# JacdacBrainRP2040_59.net
KiCad netlist of a schematic drawn in Altium Designer
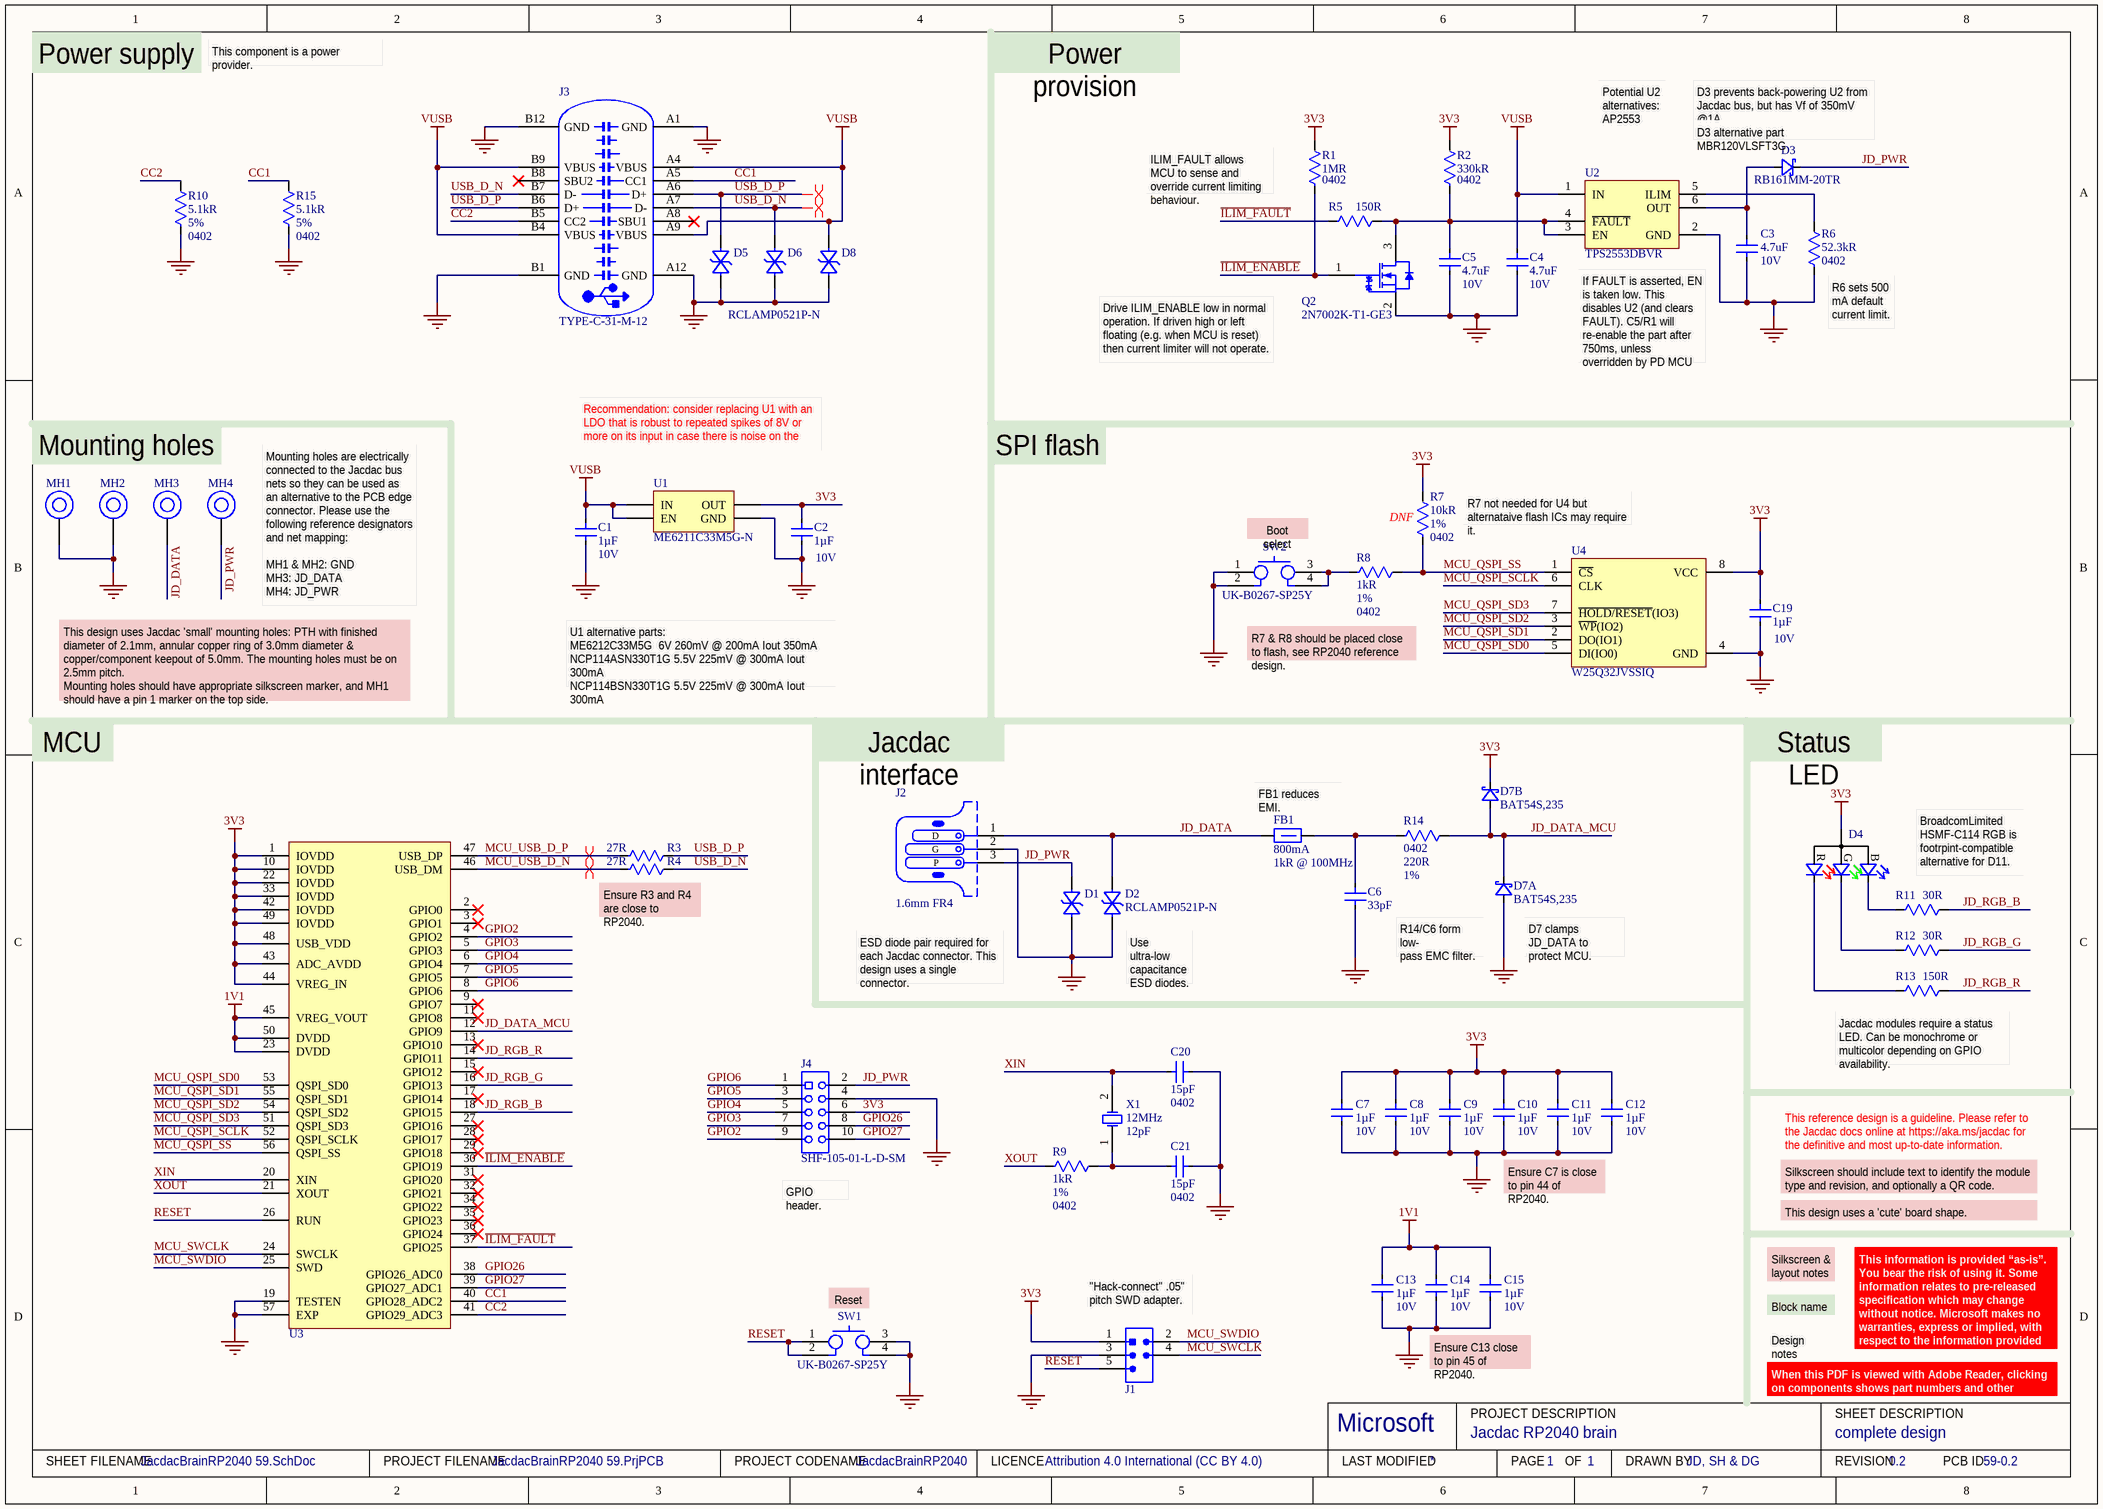
[diagram p0: JacdacBrainRP2040 59.SchDoc]

(export (version "E")
  (design (tool "Eeschema 10.0.6"))
  (components
    (comp (ref "C1")
      (value "CL05A105KP5NNNC")
      (footprint "C0402_0.55MM - without outline")
      (description "CAP CER 1UF 10V X5R 0402")
      (fields
        (field (name "MANUFACTURER") "Samsung")
        (field (name "TOLERANCE") "10%")
        (field (name "CAPACITANCE") "1µF")
        (field (name "VOLTAGE RATING") "10V")
        (field (name "CREATED") "DG")
        (field (name "CHECKED") "?")
      )
      (libsource (lib "Samsung") (part "CL05A105KP5NNNC"))
    )
    (comp (ref "C2")
      (value "CL05A105KP5NNNC")
      (footprint "C0402_0.55MM - without outline")
      (description "CAP CER 1UF 10V X5R 0402")
      (fields
        (field (name "MANUFACTURER") "Samsung")
        (field (name "TOLERANCE") "10%")
        (field (name "CAPACITANCE") "1µF")
        (field (name "VOLTAGE RATING") "10V")
        (field (name "CREATED") "DG")
        (field (name "CHECKED") "?")
      )
      (libsource (lib "Samsung") (part "CL05A105KP5NNNC"))
    )
    (comp (ref "C3")
      (value "CL05A475MP5NRNC")
      (footprint "R0402 - Without outline")
      (description "CAP CER 4.7UF 10V X5R 0402")
      (fields
        (field (name "MANUFACTURER") "Samsung")
        (field (name "TOLERANCE") "20%")
        (field (name "CAPACITANCE") "4.7uF")
        (field (name "VOLTAGE RATING") "10V")
        (field (name "CREATED BY") "D. Gakure")
        (field (name "CHECKED BY") "?")
      )
      (libsource (lib "Samsung") (part "CL05A475MP5NRNC"))
    )
    (comp (ref "C4")
      (value "CL05A475MP5NRNC")
      (footprint "R0402 - Without outline")
      (description "CAP CER 4.7UF 10V X5R 0402")
      (fields
        (field (name "MANUFACTURER") "Samsung")
        (field (name "TOLERANCE") "20%")
        (field (name "CAPACITANCE") "4.7uF")
        (field (name "VOLTAGE RATING") "10V")
        (field (name "CREATED BY") "D. Gakure")
        (field (name "CHECKED BY") "?")
      )
      (libsource (lib "Samsung") (part "CL05A475MP5NRNC"))
    )
    (comp (ref "C5")
      (value "CL05A475MP5NRNC")
      (footprint "R0402 - Without outline")
      (description "CAP CER 4.7UF 10V X5R 0402")
      (fields
        (field (name "MANUFACTURER") "Samsung")
        (field (name "TOLERANCE") "20%")
        (field (name "CAPACITANCE") "4.7uF")
        (field (name "VOLTAGE RATING") "10V")
        (field (name "CREATED BY") "D. Gakure")
        (field (name "CHECKED BY") "?")
      )
      (libsource (lib "Samsung") (part "CL05A475MP5NRNC"))
    )
    (comp (ref "C6")
      (value "CL05C330JB51PNC")
      (footprint "C0402_0.55MM - without outline")
      (description "CAP CER 33PF 50V NP0 0402")
      (fields
        (field (name "MANUFACTURER") "Samsung")
        (field (name "TOLERANCE") "5%")
        (field (name "CAPACITANCE") "33pF")
        (field (name "CHECKED") "?")
        (field (name "CREATED") "DG")
      )
      (libsource (lib "Samsung") (part "CL05C330JB51PNC"))
    )
    (comp (ref "C7")
      (value "CL05A105KP5NNNC")
      (footprint "C0402_0.55MM - without outline")
      (description "CAP CER 1UF 10V X5R 0402")
      (fields
        (field (name "MANUFACTURER") "Samsung")
        (field (name "TOLERANCE") "10%")
        (field (name "CAPACITANCE") "1µF")
        (field (name "VOLTAGE RATING") "10V")
        (field (name "CREATED") "DG")
        (field (name "CHECKED") "?")
      )
      (libsource (lib "Samsung") (part "CL05A105KP5NNNC"))
    )
    (comp (ref "C8")
      (value "CL05A105KP5NNNC")
      (footprint "C0402_0.55MM - without outline")
      (description "CAP CER 1UF 10V X5R 0402")
      (fields
        (field (name "MANUFACTURER") "Samsung")
        (field (name "TOLERANCE") "10%")
        (field (name "CAPACITANCE") "1µF")
        (field (name "VOLTAGE RATING") "10V")
        (field (name "CREATED") "DG")
        (field (name "CHECKED") "?")
      )
      (libsource (lib "Samsung") (part "CL05A105KP5NNNC"))
    )
    (comp (ref "C9")
      (value "CL05A105KP5NNNC")
      (footprint "C0402_0.55MM - without outline")
      (description "CAP CER 1UF 10V X5R 0402")
      (fields
        (field (name "MANUFACTURER") "Samsung")
        (field (name "TOLERANCE") "10%")
        (field (name "CAPACITANCE") "1µF")
        (field (name "VOLTAGE RATING") "10V")
        (field (name "CREATED") "DG")
        (field (name "CHECKED") "?")
      )
      (libsource (lib "Samsung") (part "CL05A105KP5NNNC"))
    )
    (comp (ref "C10")
      (value "CL05A105KP5NNNC")
      (footprint "C0402_0.55MM - without outline")
      (description "CAP CER 1UF 10V X5R 0402")
      (fields
        (field (name "MANUFACTURER") "Samsung")
        (field (name "TOLERANCE") "10%")
        (field (name "CAPACITANCE") "1µF")
        (field (name "VOLTAGE RATING") "10V")
        (field (name "CREATED") "DG")
        (field (name "CHECKED") "?")
      )
      (libsource (lib "Samsung") (part "CL05A105KP5NNNC"))
    )
    (comp (ref "C11")
      (value "CL05A105KP5NNNC")
      (footprint "C0402_0.55MM - without outline")
      (description "CAP CER 1UF 10V X5R 0402")
      (fields
        (field (name "MANUFACTURER") "Samsung")
        (field (name "TOLERANCE") "10%")
        (field (name "CAPACITANCE") "1µF")
        (field (name "VOLTAGE RATING") "10V")
        (field (name "CREATED") "DG")
        (field (name "CHECKED") "?")
      )
      (libsource (lib "Samsung") (part "CL05A105KP5NNNC"))
    )
    (comp (ref "C12")
      (value "CL05A105KP5NNNC")
      (footprint "C0402_0.55MM - without outline")
      (description "CAP CER 1UF 10V X5R 0402")
      (fields
        (field (name "MANUFACTURER") "Samsung")
        (field (name "TOLERANCE") "10%")
        (field (name "CAPACITANCE") "1µF")
        (field (name "VOLTAGE RATING") "10V")
        (field (name "CREATED") "DG")
        (field (name "CHECKED") "?")
      )
      (libsource (lib "Samsung") (part "CL05A105KP5NNNC"))
    )
    (comp (ref "C13")
      (value "CL05A105KP5NNNC")
      (footprint "C0402_0.55MM - without outline")
      (description "CAP CER 1UF 10V X5R 0402")
      (fields
        (field (name "MANUFACTURER") "Samsung")
        (field (name "TOLERANCE") "10%")
        (field (name "CAPACITANCE") "1µF")
        (field (name "VOLTAGE RATING") "10V")
        (field (name "CREATED") "DG")
        (field (name "CHECKED") "?")
      )
      (libsource (lib "Samsung") (part "CL05A105KP5NNNC"))
    )
    (comp (ref "C14")
      (value "CL05A105KP5NNNC")
      (footprint "C0402_0.55MM - without outline")
      (description "CAP CER 1UF 10V X5R 0402")
      (fields
        (field (name "MANUFACTURER") "Samsung")
        (field (name "TOLERANCE") "10%")
        (field (name "CAPACITANCE") "1µF")
        (field (name "VOLTAGE RATING") "10V")
        (field (name "CREATED") "DG")
        (field (name "CHECKED") "?")
      )
      (libsource (lib "Samsung") (part "CL05A105KP5NNNC"))
    )
    (comp (ref "C15")
      (value "CL05A105KP5NNNC")
      (footprint "C0402_0.55MM - without outline")
      (description "CAP CER 1UF 10V X5R 0402")
      (fields
        (field (name "MANUFACTURER") "Samsung")
        (field (name "TOLERANCE") "10%")
        (field (name "CAPACITANCE") "1µF")
        (field (name "VOLTAGE RATING") "10V")
        (field (name "CREATED") "DG")
        (field (name "CHECKED") "?")
      )
      (libsource (lib "Samsung") (part "CL05A105KP5NNNC"))
    )
    (comp (ref "C19")
      (value "CL05A105KP5NNNC")
      (footprint "C0402_0.55MM - without outline")
      (description "CAP CER 1UF 10V X5R 0402")
      (fields
        (field (name "MANUFACTURER") "Samsung")
        (field (name "TOLERANCE") "10%")
        (field (name "CAPACITANCE") "1µF")
        (field (name "VOLTAGE RATING") "10V")
        (field (name "CREATED") "DG")
        (field (name "CHECKED") "?")
      )
      (libsource (lib "Samsung") (part "CL05A105KP5NNNC"))
    )
    (comp (ref "C20")
      (value "CL05C150JB5NNNC")
      (footprint "C0402_0.55MM - without outline")
      (description "CAP CER 15PF 50V C0G/NP0 0402")
      (fields
        (field (name "MANUFACTURER") "Samsung")
        (field (name "TOLERANCE") "5%")
        (field (name "CAPACITANCE") "15pF")
        (field (name "CASE/PACKAGE") "0402")
      )
      (libsource (lib "Samsung") (part "CL05C150JB5NNNC"))
    )
    (comp (ref "C21")
      (value "CL05C150JB5NNNC")
      (footprint "C0402_0.55MM - without outline")
      (description "CAP CER 15PF 50V C0G/NP0 0402")
      (fields
        (field (name "MANUFACTURER") "Samsung")
        (field (name "TOLERANCE") "5%")
        (field (name "CAPACITANCE") "15pF")
        (field (name "CASE/PACKAGE") "0402")
      )
      (libsource (lib "Samsung") (part "CL05C150JB5NNNC"))
    )
    (comp (ref "D1")
      (value "RCLAMP0521P-N")
      (footprint "TVS 0402 - L")
      (description "Bidirectional 5V (Max) 6V 16V 3.5A (8/20us) 0402 TVS RoHS")
      (fields
        (field (name "MANUFACTURER") "Born Semiconductor")
        (field (name "CREATED BY") "D Gakure")
        (field (name "CHECKED BY") "?")
      )
      (libsource (lib "BornSemiconductor") (part "RCLAMP0521P-N"))
    )
    (comp (ref "D2")
      (value "RCLAMP0521P-N")
      (footprint "TVS 0402 - L")
      (description "Bidirectional 5V (Max) 6V 16V 3.5A (8/20us) 0402 TVS RoHS")
      (fields
        (field (name "MANUFACTURER") "Born Semiconductor")
        (field (name "MANUFACTURER PART NUMBER") "RCLAMP0521P-N")
        (field (name "CREATED BY") "D Gakure")
        (field (name "CHECKED BY") "?")
      )
      (libsource (lib "BornSemiconductor") (part "RCLAMP0521P-N"))
    )
    (comp (ref "D3")
      (value "RB161MM-20TR")
      (footprint "SOD-123F")
      (description "ROHM - RB161MM-20TR - Schottky-Gleichrichterdiode, 20 V, 1 A, Einfach, SOD-123FL, 2 Pin(s), 350 mV")
      (fields (field (name "MANUFACTURER") "Rohm") (field (name "MANUFACTURER PART NUMBER") "RB161MM-20TR"))
      (libsource (lib "Rohm") (part "RB161MM-20TR"))
    )
    (comp (ref "D4")
      (value "TZ-P4-1615RGBTCA1-0.55T")
      (footprint "TZ-P4-1615RGBTCA1-0.55T")
      (description "1615 Light Emitting Diodes (LED) RoHS")
      (fields
        (field (name "MANUFACTURER") "TUOZHAN")
        (field (name "CREATED BY") "D. Gakure")
        (field (name "CHECKED BY") "?")
      )
      (libsource (lib "Tuozhan") (part "TZ-P4-1615RGBTCA1-0.55T"))
    )
    (comp (ref "D5")
      (value "RCLAMP0521P-N")
      (footprint "TVS 0402 - L")
      (description "Bidirectional 5V (Max) 6V 16V 3.5A (8/20us) 0402 TVS RoHS")
      (fields
        (field (name "MANUFACTURER") "Born Semiconductor")
        (field (name "CREATED BY") "D Gakure")
        (field (name "CHECKED BY") "?")
      )
      (libsource (lib "BornSemiconductor") (part "RCLAMP0521P-N"))
    )
    (comp (ref "D6")
      (value "RCLAMP0521P-N")
      (footprint "TVS 0402 - L")
      (description "Bidirectional 5V (Max) 6V 16V 3.5A (8/20us) 0402 TVS RoHS")
      (fields
        (field (name "MANUFACTURER") "Born Semiconductor")
        (field (name "CREATED BY") "D Gakure")
        (field (name "CHECKED BY") "?")
      )
      (libsource (lib "BornSemiconductor") (part "RCLAMP0521P-N"))
    )
    (comp (ref "D7")
      (value "BAT54S")
      (footprint "NXP-BAT54S-TO-236AB - without outline")
      (description "DIODE ARRAY SCHOTTKY 30V SOT23")
      (fields (field (name "MANUFACTURER") "Nexperia") (field (name "MANUFACTURER PART NUMBER") "BAT54S,235"))
      (libsource (lib "NXP") (part "BAT54S"))
    )
    (comp (ref "D8")
      (value "RCLAMP0521P-N")
      (footprint "TVS 0402 - L")
      (description "Bidirectional 5V (Max) 6V 16V 3.5A (8/20us) 0402 TVS RoHS")
      (fields
        (field (name "MANUFACTURER") "Born Semiconductor")
        (field (name "MANUFACTURER PART NUMBER") "RCLAMP0521P-N")
        (field (name "CREATED BY") "D Gakure")
        (field (name "CHECKED BY") "?")
      )
      (libsource (lib "BornSemiconductor") (part "RCLAMP0521P-N"))
    )
    (comp (ref "FB1")
      (value "TDK MPZ1608S102ATA00")
      (footprint "TDK MPZ1608 0.8mm - without outline")
      (description "0603 1k@100MHz 0.8A chip")
      (fields
        (field (name "TOLERANCE") "25%")
        (field (name "MANUFACTURER") "TDK")
        (field (name "CURRENT RATING") "800mA")
        (field (name "IMPEDANCE") "1kR @ 100MHz")
      )
      (libsource (lib "TDK") (part "TDK MPZ1608S102ATA00"))
    )
    (comp (ref "J1")
      (value "Hack Connect Mini 1.27 mm pitch 2-row")
      (footprint "HACK_CONNECT_MINI_5_X_1_27")
      (libsource (lib "generic-con") (part "HACK_CONNECT_MINI"))
    )
    (comp (ref "J2")
      (value "3 pin JACDAC edge connector")
      (footprint "JACDAC_EDGE_CONNECTOR_NO_TRACES")
      (description "3 pin Jacdac edge connector 1.27mm pitch")
      (fields
        (field (name "MANUFACTURER PART NUMBER") "JACDAC_EDGE_CONNECTOR")
        (field (name "PCB TYPE") "1.6mm FR4")
        (field (name "CHECKED BY") "?")
        (field (name "CREATED BY") "D. Gakure")
      )
      (libsource (lib "generic-con") (part "Jacdac edge connector"))
    )
    (comp (ref "J3")
      (value "TYPE-C-31-M-12")
      (footprint "TYPE-C-31-M-12")
      (description "USB - Type C Female 16 USB Connectors RoHS")
      (fields
        (field (name "MANUFACTURER") "Korean Hroparts Elec")
        (field (name "MANUFACTURER PART NUMBER") "TYPE-C-31-M-12")
      )
      (libsource (lib "KoreanHropartsElec") (part "TYPE-C-31-M-12"))
    )
    (comp (ref "J4")
      (value "SHF-105-01-L-D-SM-whitesch")
      (footprint "Samtec SHF-105-01-L-D-SM - NO SILKSCREEN")
      (description "Standard Card Edge Connectors .050 Mini Edge Card Connector, Vertical")
      (fields
        (field (name "MANUFACTURER") "Samtec")
        (field (name "MANUFACTURER PART NUMBER") "SHF-105-01-L-D-SM")
      )
      (libsource (lib "Samtec") (part "SHF-105-01-L-D-SM-whitesch"))
    )
    (comp (ref "MH1")
      (value "MH_5.0MMK_3.0MMC_2.1MMD_PTH")
      (footprint "MH_5.0MMK_3.0MMC_2.1MMD_PTH")
      (description "Mounting Hole 5.0mm keepout, 3.0mm annualar ring and 2.1mm Drill PTH")
      (libsource (lib "generic") (part "MH_5.0MMK_3.0MMC_2.1MMD_PTH"))
    )
    (comp (ref "MH2")
      (value "MH_5.0MMK_3.0MMC_2.1MMD_PTH")
      (footprint "MH_5.0MMK_3.0MMC_2.1MMD_PTH")
      (description "Mounting Hole 5.0mm keepout, 3.0mm annualar ring and 2.1mm Drill PTH")
      (libsource (lib "generic") (part "MH_5.0MMK_3.0MMC_2.1MMD_PTH"))
    )
    (comp (ref "MH3")
      (value "MH_5.0MMK_3.0MMC_2.1MMD_PTH")
      (footprint "MH_5.0MMK_3.0MMC_2.1MMD_PTH")
      (description "Mounting Hole 5.0mm keepout, 3.0mm annualar ring and 2.1mm Drill PTH")
      (libsource (lib "generic") (part "MH_5.0MMK_3.0MMC_2.1MMD_PTH"))
    )
    (comp (ref "MH4")
      (value "MH_5.0MMK_3.0MMC_2.1MMD_PTH")
      (footprint "MH_5.0MMK_3.0MMC_2.1MMD_PTH")
      (description "Mounting Hole 5.0mm keepout, 3.0mm annualar ring and 2.1mm Drill PTH")
      (libsource (lib "generic") (part "MH_5.0MMK_3.0MMC_2.1MMD_PTH"))
    )
    (comp (ref "Q2")
      (value "2N7002K-T1-GE3")
      (footprint "SOT-23-3 (TO-236)")
      (description "Trans MOSFET N-CH Si 60V 0.3A 3-Pin SOT-23 T/R")
      (fields
        (field (name "MANUFACTURER") "Vishay")
        (field (name "VOLTAGE") "60V")
        (field (name "MANUFACTURER PART NUMBER") "2N7002K-T1-GE3")
      )
      (libsource (lib "Vishay") (part "2N7002K-T1-GE3"))
    )
    (comp (ref "R1")
      (value "~")
      (footprint "R0402 - Without outline")
      (description "RES SMD 1M OHM 1% 1/16W 0402")
      (fields
        (field (name "MANUFACTURER") "Yageo")
        (field (name "MANUFACTURER PART NUMBER") "RC0402FR-071ML")
        (field (name "RESISTANCE") "1MR")
        (field (name "CASE CODE (IMPERIAL)") "0402")
        (field (name "CREATED BY") "D. Gakure")
        (field (name "CHECKED BY") "?")
      )
      (libsource (lib "Yageo") (part "RC0402FR-071ML"))
    )
    (comp (ref "R2")
      (value "RC0402FR-07330KL")
      (footprint "R0402 - Without outline")
      (description "RES SMD 330K OHM 1% 1/16W 0402")
      (fields
        (field (name "MANUFACTURER") "Yageo")
        (field (name "RESISTANCE") "330kR")
        (field (name "TOLERANCE") "1%")
        (field (name "SIZE CODE") "0402")
        (field (name "CREATED BY") "D Gakure")
        (field (name "CHECKED BY") "?")
      )
      (libsource (lib "Yageo") (part "RC0402FR-07330KL"))
    )
    (comp (ref "R3")
      (value "RC0402FR-0727RL")
      (footprint "R0402 - Without outline")
      (description "RES SMD 27 OHM 1% 1/16W 0402")
      (fields
        (field (name "MANUFACTURER") "Yageo")
        (field (name "TOLERANCE") "1%")
        (field (name "RESISTANCE") "27R")
      )
      (libsource (lib "Yageo") (part "RC0402FR-0727RL"))
    )
    (comp (ref "R4")
      (value "RC0402FR-0727RL")
      (footprint "R0402 - Without outline")
      (description "RES SMD 27 OHM 1% 1/16W 0402")
      (fields
        (field (name "MANUFACTURER") "Yageo")
        (field (name "TOLERANCE") "1%")
        (field (name "RESISTANCE") "27R")
      )
      (libsource (lib "Yageo") (part "RC0402FR-0727RL"))
    )
    (comp (ref "R5")
      (value "RC0402FR-07150RL")
      (footprint "R0402 - Without outline")
      (description "RES SMD 150 OHM 1% 1/16W 0402")
      (fields
        (field (name "MANUFACTURER") "Yageo")
        (field (name "RESISTANCE") "150R")
        (field (name "TOLERANCE") "1%")
        (field (name "CREATED BY") "D. Gakure")
        (field (name "CHECKED BY") "?")
      )
      (libsource (lib "Yageo") (part "RC0402FR-07150RL"))
    )
    (comp (ref "R6")
      (value "RC0402FR-0752K3L")
      (footprint "R0402 - Without outline")
      (description "RES SMD 52.3K OHM 1% 1/16W 0402")
      (fields
        (field (name "MANUFACTURER") "Yageo")
        (field (name "RESISTANCE") "52.3kR")
        (field (name "TOLERANCE") "1%")
        (field (name "CASE CODE (IMPERIAL)") "0402")
        (field (name "CREATED BY") "D. Gakure")
        (field (name "CHECKED BY") "?")
      )
      (libsource (lib "Yageo") (part "RC0402FR-0752K3L"))
    )
    (comp (ref "R7")
      (value "10k")
      (footprint "R0402 - Without outline")
      (description "RES SMD 10K OHM 1% 1/16W 0402")
      (fields
        (field (name "MANUFACTURER") "Yageo")
        (field (name "MANUFACTURER PART NUMBER") "RC0402FR-0710KL")
        (field (name "RESISTANCE") "10kR")
        (field (name "TOLERANCE") "1%")
        (field (name "CASE CODE (IMPERIAL)") "0402")
        (field (name "CHECKED") "?")
        (field (name "CREATED") "DG")
      )
      (libsource (lib "Yageo") (part "RC0402FR-0710KL"))
    )
    (comp (ref "R8")
      (value "RC0402FR-071KL")
      (footprint "R0402 - Without outline")
      (description "RES SMD 1K OHM 1% 1/16W 0402")
      (fields
        (field (name "MANUFACTURER") "Yageo")
        (field (name "RESISTANCE") "1kR")
        (field (name "TOLERANCE") "1%")
        (field (name "CASE CODE (IMPERIAL)") "0402")
        (field (name "CREATED") "D.G")
        (field (name "CHECKED") "?")
      )
      (libsource (lib "Yageo") (part "RC0402FR-071KL"))
    )
    (comp (ref "R9")
      (value "RC0402FR-071KL")
      (footprint "R0402 - Without outline")
      (description "RES SMD 1K OHM 1% 1/16W 0402")
      (fields
        (field (name "MANUFACTURER") "Yageo")
        (field (name "RESISTANCE") "1kR")
        (field (name "TOLERANCE") "1%")
        (field (name "CASE CODE (IMPERIAL)") "0402")
        (field (name "CREATED") "D.G")
        (field (name "CHECKED") "?")
      )
      (libsource (lib "Yageo") (part "RC0402FR-071KL"))
    )
    (comp (ref "R10")
      (value "RC0402JR-075K1L")
      (footprint "R0402 - Without outline")
      (description "RES SMD 5.1K OHM 5% 1/16W 0402")
      (fields
        (field (name "MANUFACTURER") "Yageo")
        (field (name "RESISTANCE") "5.1kR")
        (field (name "TOLERANCE") "5%")
        (field (name "CASE CODE (IMPERIAL)") "0402")
        (field (name "CREATED BY") "D. Gakure")
        (field (name "CHECKED BY") "?")
      )
      (libsource (lib "Yageo") (part "RC0402JR-075K1L"))
    )
    (comp (ref "R11")
      (value "RC0402FR-0730RL")
      (footprint "R0402 - Without outline")
      (description "RES SMD 30 OHM 1% 1/16W 0402")
      (fields
        (field (name "MANUFACTURER") "Yageo")
        (field (name "RESISTANCE") "30R")
        (field (name "TOLERANCE") "1%")
        (field (name "CREATED BY") "D. Gakure")
        (field (name "CHECKED BY") "?")
      )
      (libsource (lib "Yageo") (part "RC0402FR-0730RL"))
    )
    (comp (ref "R12")
      (value "RC0402FR-0730RL")
      (footprint "R0402 - Without outline")
      (description "RES SMD 30 OHM 1% 1/16W 0402")
      (fields
        (field (name "MANUFACTURER") "Yageo")
        (field (name "RESISTANCE") "30R")
        (field (name "TOLERANCE") "1%")
        (field (name "CREATED BY") "D. Gakure")
        (field (name "CHECKED BY") "?")
      )
      (libsource (lib "Yageo") (part "RC0402FR-0730RL"))
    )
    (comp (ref "R13")
      (value "RC0402FR-07150RL")
      (footprint "R0402 - Without outline")
      (description "RES SMD 150 OHM 1% 1/16W 0402")
      (fields
        (field (name "MANUFACTURER") "Yageo")
        (field (name "RESISTANCE") "150R")
        (field (name "TOLERANCE") "1%")
        (field (name "CREATED BY") "D. Gakure")
        (field (name "CHECKED BY") "?")
      )
      (libsource (lib "Yageo") (part "RC0402FR-07150RL"))
    )
    (comp (ref "R14")
      (value "RC0402FR-07220RL")
      (footprint "R0402 - Without outline")
      (description "RES SMD 220 OHM 1% 1/16W 0402")
      (fields
        (field (name "MANUFACTURER") "Yageo")
        (field (name "CASE CODE (IMPERIAL)") "0402")
        (field (name "RESISTANCE") "220R")
        (field (name "TOLERANCE") "1%")
        (field (name "CREATED") "D.G")
        (field (name "CHECKED") "?")
      )
      (libsource (lib "Yageo") (part "RC0402FR-07220RL"))
    )
    (comp (ref "R15")
      (value "RC0402JR-075K1L")
      (footprint "R0402 - Without outline")
      (description "RES SMD 5.1K OHM 5% 1/16W 0402")
      (fields
        (field (name "MANUFACTURER") "Yageo")
        (field (name "RESISTANCE") "5.1kR")
        (field (name "TOLERANCE") "5%")
        (field (name "CASE CODE (IMPERIAL)") "0402")
        (field (name "CREATED BY") "D. Gakure")
        (field (name "CHECKED BY") "?")
      )
      (libsource (lib "Yageo") (part "RC0402JR-075K1L"))
    )
    (comp (ref "SW1")
      (value "UK-B0267-SP25Y")
      (footprint "USAKRO-UK-B0267-SP25Y")
      (description "SWITCH TACTILE SSPST 50mA @ 12VDC")
      (fields
        (field (name "MANUFACTURER") "USAKRO")
        (field (name "MANUFACTURER PART NUMBER") "UK-B0267-SP25Y")
      )
      (libsource (lib "Usakro") (part "UK-B0267-SP25Y"))
    )
    (comp (ref "SW2")
      (value "UK-B0267-SP25Y")
      (footprint "USAKRO-UK-B0267-SP25Y")
      (description "SWITCH TACTILE SSPST 50mA @ 12VDC")
      (fields
        (field (name "MANUFACTURER") "USAKRO")
        (field (name "MANUFACTURER PART NUMBER") "UK-B0267-SP25Y")
      )
      (libsource (lib "Usakro") (part "UK-B0267-SP25Y"))
    )
    (comp (ref "U1")
      (value "ME6211C33M5G-N")
      (footprint "MICRONE-SOT23-5")
      (description "6V 260mV @ 200mA(typ) - - Fixed 3.3V SOT-23-5 Linear Voltage Regulators (LDO) ROHS")
      (fields
        (field (name "MANUFACTURER") "MICRONE(Nanjing Micro One Elec)")
        (field (name "MANUFACTURER PART NUMBER") "ME6211C33M5G-N")
        (field (name "CREATED") "DG")
        (field (name "CHECKED") "?")
      )
      (libsource (lib "MICRONE(NanjingMicroOneElec)") (part "ME6211C33M5G-N"))
    )
    (comp (ref "U2")
      (value "TPS2553DBVR")
      (footprint "TI-TPS2553 - without_outline")
      (description "IC PWR SWITCH N-CHAN 1:1 SOT23-6")
      (fields
        (field (name "MANUFACTURER") "Texas Instruments")
        (field (name "MANUFACTURER PART NUMBER") "TPS2553DBVR")
      )
      (libsource (lib "TexasInstruments") (part "TPS2553DBVR"))
    )
    (comp (ref "U3")
      (value "RP2040")
      (footprint "RP2040")
      (description "QFN-56_7x7 MCU")
      (fields (field (name "MANUFACTURER") "Raspberry Pi"))
      (libsource (lib "RaspberryPi") (part "RP2040"))
    )
    (comp (ref "U4")
      (value "~")
      (footprint "8-SOIC")
      (description "FLASH - NOR Memory IC 32Mb (4M x 8) SPI - Quad I/O 133 MHz 8-SOIC")
      (fields
        (field (name "MANUFACTURER") "Winbond")
        (field (name "MANUFACTURER PART NUMBER") "W25Q32JVSSIQ")
      )
      (libsource (lib "WinbondElectronics") (part "W25Q32JVSSIQ"))
    )
    (comp (ref "X1")
      (value "12MHz")
      (footprint "SMD-5032_2P")
      (description "12MHz ±30ppm 12pF 50Ω SMD-5032_2P SMD Crystal Resonators RoHS")
      (fields
        (field (name "MANUFACTURER") "TXC")
        (field (name "MANUFACTURER PART NUMBER") "7A12000053")
        (field (name "LOAD CAPACITANCE") "12pF")
      )
      (libsource (lib "TXC") (part "7A12000053"))
    )
  )
  (nets
    (net (code "1") (name "/CC1") (class "Default")
      (node (ref "J3") (pin "A5") (pinfunction "CC1_A5") (pintype "passive"))
      (node (ref "R15") (pin "1") (pinfunction "1_1") (pintype "passive"))
      (node (ref "U3") (pin "40") (pinfunction "GPIO28_ADC2_40") (pintype "passive"))
    )
    (net (code "2") (name "/CC2") (class "Default")
      (node (ref "J3") (pin "B5") (pinfunction "CC2_B5") (pintype "passive"))
      (node (ref "R10") (pin "1") (pinfunction "1_1") (pintype "passive"))
      (node (ref "U3") (pin "41") (pinfunction "GPIO29_ADC3_41") (pintype "passive"))
    )
    (net (code "3") (name "/GPIO2") (class "Default")
      (node (ref "J4") (pin "9") (pinfunction "9_9") (pintype "passive"))
      (node (ref "U3") (pin "4") (pinfunction "GPIO2_4") (pintype "passive"))
    )
    (net (code "4") (name "/GPIO3") (class "Default")
      (node (ref "J4") (pin "7") (pinfunction "7_7") (pintype "passive"))
      (node (ref "U3") (pin "5") (pinfunction "GPIO3_5") (pintype "passive"))
    )
    (net (code "5") (name "/GPIO4") (class "Default")
      (node (ref "J4") (pin "5") (pinfunction "5_5") (pintype "passive"))
      (node (ref "U3") (pin "6") (pinfunction "GPIO4_6") (pintype "passive"))
    )
    (net (code "6") (name "/GPIO5") (class "Default")
      (node (ref "J4") (pin "3") (pinfunction "3_3") (pintype "passive"))
      (node (ref "U3") (pin "7") (pinfunction "GPIO5_7") (pintype "passive"))
    )
    (net (code "7") (name "/GPIO6") (class "Default")
      (node (ref "J4") (pin "1") (pinfunction "1_1") (pintype "passive"))
      (node (ref "U3") (pin "8") (pinfunction "GPIO6_8") (pintype "passive"))
    )
    (net (code "8") (name "/GPIO26") (class "Default")
      (node (ref "J4") (pin "8") (pinfunction "8_8") (pintype "passive"))
      (node (ref "U3") (pin "38") (pinfunction "GPIO26_ADC0_38") (pintype "passive"))
    )
    (net (code "9") (name "/GPIO27") (class "Default")
      (node (ref "J4") (pin "10") (pinfunction "10_10") (pintype "passive"))
      (node (ref "U3") (pin "39") (pinfunction "GPIO27_ADC1_39") (pintype "passive"))
    )
    (net (code "10") (name "/JD_DATA") (class "Default")
      (node (ref "D2") (pin "1") (pinfunction "K_1") (pintype "passive"))
      (node (ref "FB1") (pin "1") (pinfunction "1_1") (pintype "passive"))
      (node (ref "J2") (pin "1") (pinfunction "D_1") (pintype "passive"))
      (node (ref "MH3") (pin "1") (pinfunction "1_1") (pintype "passive"))
    )
    (net (code "11") (name "/JD_DATA_MCU") (class "Default")
      (node (ref "D7") (pin "3") (pinfunction "A_3") (pintype "passive"))
      (node (ref "R14") (pin "1") (pinfunction "1_1") (pintype "passive"))
      (node (ref "U3") (pin "12") (pinfunction "GPIO9_12") (pintype "passive"))
    )
    (net (code "12") (name "/JD_PWR") (class "Default")
      (node (ref "D1") (pin "1") (pinfunction "K_1") (pintype "passive"))
      (node (ref "D3") (pin "1") (pinfunction "K_1") (pintype "passive"))
      (node (ref "J2") (pin "3") (pinfunction "P_3") (pintype "passive"))
      (node (ref "J4") (pin "2") (pinfunction "2_2") (pintype "passive"))
      (node (ref "MH4") (pin "1") (pinfunction "1_1") (pintype "passive"))
    )
    (net (code "13") (name "/JD_RGB_B") (class "Default")
      (node (ref "R11") (pin "2") (pinfunction "2_2") (pintype "passive"))
      (node (ref "U3") (pin "18") (pinfunction "GPIO15_18") (pintype "passive"))
    )
    (net (code "14") (name "/JD_RGB_G") (class "Default")
      (node (ref "R12") (pin "2") (pinfunction "2_2") (pintype "passive"))
      (node (ref "U3") (pin "16") (pinfunction "GPIO13_16") (pintype "passive"))
    )
    (net (code "15") (name "/JD_RGB_R") (class "Default")
      (node (ref "R13") (pin "2") (pinfunction "2_2") (pintype "passive"))
      (node (ref "U3") (pin "14") (pinfunction "GPIO11_14") (pintype "passive"))
    )
    (net (code "16") (name "/MCU_QSPI_SCLK") (class "Default")
      (node (ref "U3") (pin "52") (pinfunction "QSPI_SCLK_52") (pintype "passive"))
      (node (ref "U4") (pin "6") (pinfunction "CLK_6") (pintype "passive"))
    )
    (net (code "17") (name "/MCU_QSPI_SD0") (class "Default")
      (node (ref "U3") (pin "53") (pinfunction "QSPI_SD0_53") (pintype "passive"))
      (node (ref "U4") (pin "5") (pinfunction "DI(IO0)_5") (pintype "passive"))
    )
    (net (code "18") (name "/MCU_QSPI_SD1") (class "Default")
      (node (ref "U3") (pin "55") (pinfunction "QSPI_SD1_55") (pintype "passive"))
      (node (ref "U4") (pin "2") (pinfunction "DO(IO1)_2") (pintype "passive"))
    )
    (net (code "19") (name "/MCU_QSPI_SD2") (class "Default")
      (node (ref "U3") (pin "54") (pinfunction "QSPI_SD2_54") (pintype "passive"))
      (node (ref "U4") (pin "3") (pinfunction "~{WP}(IO2)_3") (pintype "passive"))
    )
    (net (code "20") (name "/MCU_QSPI_SD3") (class "Default")
      (node (ref "U3") (pin "51") (pinfunction "QSPI_SD3_51") (pintype "passive"))
      (node (ref "U4") (pin "7") (pinfunction "~{HOLD/RESET}(IO3)_7") (pintype "passive"))
    )
    (net (code "21") (name "/MCU_QSPI_SS") (class "Default")
      (node (ref "R7") (pin "2") (pinfunction "2_2") (pintype "passive"))
      (node (ref "R8") (pin "1") (pinfunction "1_1") (pintype "passive"))
      (node (ref "U3") (pin "56") (pinfunction "QSPI_SS_56") (pintype "passive"))
      (node (ref "U4") (pin "1") (pinfunction "~{CS}_1") (pintype "passive"))
    )
    (net (code "22") (name "/MCU_SWCLK") (class "Default")
      (node (ref "J1") (pin "4") (pinfunction "SWCLK_4") (pintype "passive"))
      (node (ref "U3") (pin "24") (pinfunction "SWCLK_24") (pintype "passive"))
    )
    (net (code "23") (name "/MCU_SWDIO") (class "Default")
      (node (ref "J1") (pin "2") (pinfunction "SWDIO_2") (pintype "passive"))
      (node (ref "U3") (pin "25") (pinfunction "SWD_25") (pintype "passive"))
    )
    (net (code "24") (name "/MCU_USB_D_N") (class "Default")
      (node (ref "R4") (pin "1") (pinfunction "1_1") (pintype "passive"))
      (node (ref "U3") (pin "46") (pinfunction "USB_DM_46") (pintype "passive"))
    )
    (net (code "25") (name "/MCU_USB_D_P") (class "Default")
      (node (ref "R3") (pin "1") (pinfunction "1_1") (pintype "passive"))
      (node (ref "U3") (pin "47") (pinfunction "USB_DP_47") (pintype "passive"))
    )
    (net (code "26") (name "/RESET") (class "Default")
      (node (ref "J1") (pin "5") (pinfunction "RESET_5") (pintype "passive"))
      (node (ref "SW1") (pin "1") (pinfunction "1_1") (pintype "passive"))
      (node (ref "SW1") (pin "2") (pinfunction "2_2") (pintype "passive"))
      (node (ref "U3") (pin "26") (pinfunction "RUN_26") (pintype "passive"))
    )
    (net (code "27") (name "/USB_D_N") (class "Default")
      (node (ref "D6") (pin "1") (pinfunction "K_1") (pintype "passive"))
      (node (ref "J3") (pin "A7") (pinfunction "D-_A7") (pintype "passive"))
      (node (ref "J3") (pin "B7") (pinfunction "D-_B7") (pintype "passive"))
      (node (ref "R4") (pin "2") (pinfunction "2_2") (pintype "passive"))
    )
    (net (code "28") (name "/USB_D_P") (class "Default")
      (node (ref "D5") (pin "1") (pinfunction "K_1") (pintype "passive"))
      (node (ref "J3") (pin "A6") (pinfunction "D+_A6") (pintype "passive"))
      (node (ref "J3") (pin "B6") (pinfunction "D+_B6") (pintype "passive"))
      (node (ref "R3") (pin "2") (pinfunction "2_2") (pintype "passive"))
    )
    (net (code "29") (name "/XIN") (class "Default")
      (node (ref "C20") (pin "1") (pinfunction "1_1") (pintype "passive"))
      (node (ref "U3") (pin "20") (pinfunction "XIN_20") (pintype "passive"))
      (node (ref "X1") (pin "2") (pinfunction "OSC2/OSC1_2") (pintype "passive"))
    )
    (net (code "30") (name "/XOUT") (class "Default")
      (node (ref "R9") (pin "2") (pinfunction "2_2") (pintype "passive"))
      (node (ref "U3") (pin "21") (pinfunction "XOUT_21") (pintype "passive"))
    )
    (net (code "31") (name "/~{ILIM_ENABLE}") (class "Default")
      (node (ref "Q2") (pin "1") (pinfunction "G_1") (pintype "passive"))
      (node (ref "R1") (pin "2") (pinfunction "2_2") (pintype "passive"))
      (node (ref "U3") (pin "30") (pinfunction "GPIO19_30") (pintype "passive"))
    )
    (net (code "32") (name "/~{ILIM_FAULT}") (class "Default")
      (node (ref "R5") (pin "1") (pinfunction "1_1") (pintype "passive"))
      (node (ref "U3") (pin "37") (pinfunction "GPIO25_37") (pintype "passive"))
    )
    (net (code "33") (name "1V1") (class "Default")
      (node (ref "C13") (pin "2") (pinfunction "2_2") (pintype "passive"))
      (node (ref "C14") (pin "2") (pinfunction "2_2") (pintype "passive"))
      (node (ref "C15") (pin "2") (pinfunction "2_2") (pintype "passive"))
      (node (ref "U3") (pin "23") (pinfunction "DVDD_23") (pintype "passive"))
      (node (ref "U3") (pin "45") (pinfunction "VREG_VOUT_45") (pintype "passive"))
      (node (ref "U3") (pin "50") (pinfunction "DVDD_50") (pintype "passive"))
    )
    (net (code "34") (name "3V3") (class "Default")
      (node (ref "C10") (pin "2") (pinfunction "2_2") (pintype "passive"))
      (node (ref "C11") (pin "2") (pinfunction "2_2") (pintype "passive"))
      (node (ref "C12") (pin "2") (pinfunction "2_2") (pintype "passive"))
      (node (ref "C19") (pin "2") (pinfunction "2_2") (pintype "passive"))
      (node (ref "C2") (pin "2") (pinfunction "2_2") (pintype "passive"))
      (node (ref "C7") (pin "2") (pinfunction "2_2") (pintype "passive"))
      (node (ref "C8") (pin "2") (pinfunction "2_2") (pintype "passive"))
      (node (ref "C9") (pin "2") (pinfunction "2_2") (pintype "passive"))
      (node (ref "D4") (pin "1") (pinfunction "A_1") (pintype "passive"))
      (node (ref "D7") (pin "2") (pinfunction "K_2") (pintype "passive"))
      (node (ref "J1") (pin "1") (pinfunction "VCC_1") (pintype "passive"))
      (node (ref "J4") (pin "6") (pinfunction "6_6") (pintype "passive"))
      (node (ref "R1") (pin "1") (pinfunction "1_1") (pintype "passive"))
      (node (ref "R2") (pin "1") (pinfunction "1_1") (pintype "passive"))
      (node (ref "R7") (pin "1") (pinfunction "1_1") (pintype "passive"))
      (node (ref "U1") (pin "5") (pinfunction "OUT_5") (pintype "passive"))
      (node (ref "U3") (pin "1") (pinfunction "IOVDD_1") (pintype "passive"))
      (node (ref "U3") (pin "10") (pinfunction "IOVDD_10") (pintype "passive"))
      (node (ref "U3") (pin "22") (pinfunction "IOVDD_22") (pintype "passive"))
      (node (ref "U3") (pin "33") (pinfunction "IOVDD_33") (pintype "passive"))
      (node (ref "U3") (pin "42") (pinfunction "IOVDD_42") (pintype "passive"))
      (node (ref "U3") (pin "43") (pinfunction "ADC_AVDD_43") (pintype "passive"))
      (node (ref "U3") (pin "44") (pinfunction "VREG_IN_44") (pintype "passive"))
      (node (ref "U3") (pin "48") (pinfunction "USB_VDD_48") (pintype "passive"))
      (node (ref "U3") (pin "49") (pinfunction "IOVDD_49") (pintype "passive"))
      (node (ref "U4") (pin "8") (pinfunction "VCC_8") (pintype "power_in"))
    )
    (net (code "35") (name "GND") (class "Default")
      (node (ref "C1") (pin "1") (pinfunction "1_1") (pintype "passive"))
      (node (ref "C10") (pin "1") (pinfunction "1_1") (pintype "passive"))
      (node (ref "C11") (pin "1") (pinfunction "1_1") (pintype "passive"))
      (node (ref "C12") (pin "1") (pinfunction "1_1") (pintype "passive"))
      (node (ref "C13") (pin "1") (pinfunction "1_1") (pintype "passive"))
      (node (ref "C14") (pin "1") (pinfunction "1_1") (pintype "passive"))
      (node (ref "C15") (pin "1") (pinfunction "1_1") (pintype "passive"))
      (node (ref "C19") (pin "1") (pinfunction "1_1") (pintype "passive"))
      (node (ref "C2") (pin "1") (pinfunction "1_1") (pintype "passive"))
      (node (ref "C20") (pin "2") (pinfunction "2_2") (pintype "passive"))
      (node (ref "C21") (pin "2") (pinfunction "2_2") (pintype "passive"))
      (node (ref "C3") (pin "1") (pinfunction "1_1") (pintype "passive"))
      (node (ref "C4") (pin "1") (pinfunction "1_1") (pintype "passive"))
      (node (ref "C5") (pin "1") (pinfunction "1_1") (pintype "passive"))
      (node (ref "C6") (pin "1") (pinfunction "1_1") (pintype "passive"))
      (node (ref "C7") (pin "1") (pinfunction "1_1") (pintype "passive"))
      (node (ref "C8") (pin "1") (pinfunction "1_1") (pintype "passive"))
      (node (ref "C9") (pin "1") (pinfunction "1_1") (pintype "passive"))
      (node (ref "D1") (pin "2") (pinfunction "A_2") (pintype "passive"))
      (node (ref "D2") (pin "2") (pinfunction "A_2") (pintype "passive"))
      (node (ref "D5") (pin "2") (pinfunction "A_2") (pintype "passive"))
      (node (ref "D6") (pin "2") (pinfunction "A_2") (pintype "passive"))
      (node (ref "D7") (pin "1") (pinfunction "A_1") (pintype "passive"))
      (node (ref "D8") (pin "2") (pinfunction "A_2") (pintype "passive"))
      (node (ref "J1") (pin "3") (pinfunction "GND_3") (pintype "passive"))
      (node (ref "J2") (pin "2") (pinfunction "G_2") (pintype "passive"))
      (node (ref "J3") (pin "A1") (pinfunction "GND_A1") (pintype "passive"))
      (node (ref "J3") (pin "A12") (pinfunction "GND_A12") (pintype "passive"))
      (node (ref "J3") (pin "B1") (pinfunction "GND_B1") (pintype "passive"))
      (node (ref "J3") (pin "B12") (pinfunction "GND_B12") (pintype "passive"))
      (node (ref "J4") (pin "4") (pinfunction "4_4") (pintype "passive"))
      (node (ref "MH1") (pin "1") (pinfunction "1_1") (pintype "passive"))
      (node (ref "MH2") (pin "1") (pinfunction "1_1") (pintype "passive"))
      (node (ref "Q2") (pin "2") (pinfunction "S_2") (pintype "passive"))
      (node (ref "R10") (pin "2") (pinfunction "2_2") (pintype "passive"))
      (node (ref "R15") (pin "2") (pinfunction "2_2") (pintype "passive"))
      (node (ref "R6") (pin "1") (pinfunction "1_1") (pintype "passive"))
      (node (ref "SW1") (pin "3") (pinfunction "3_3") (pintype "passive"))
      (node (ref "SW1") (pin "4") (pinfunction "4_4") (pintype "passive"))
      (node (ref "SW2") (pin "1") (pinfunction "1_1") (pintype "passive"))
      (node (ref "SW2") (pin "2") (pinfunction "2_2") (pintype "passive"))
      (node (ref "U1") (pin "2") (pinfunction "GND_2") (pintype "passive"))
      (node (ref "U2") (pin "2") (pinfunction "GND_2") (pintype "passive"))
      (node (ref "U3") (pin "19") (pinfunction "TESTEN_19") (pintype "passive"))
      (node (ref "U3") (pin "57") (pinfunction "EXP_57") (pintype "passive"))
      (node (ref "U4") (pin "4") (pinfunction "GND_4") (pintype "power_in"))
    )
    (net (code "36") (name "Net-(C6-Pad2)") (class "Default")
      (node (ref "C6") (pin "2") (pinfunction "2_2") (pintype "passive"))
      (node (ref "FB1") (pin "2") (pinfunction "2_2") (pintype "passive"))
      (node (ref "R14") (pin "2") (pinfunction "2_2") (pintype "passive"))
    )
    (net (code "37") (name "Net-(D3-A)") (class "Default")
      (node (ref "C3") (pin "2") (pinfunction "2_2") (pintype "passive"))
      (node (ref "D3") (pin "2") (pinfunction "A_2") (pintype "passive"))
      (node (ref "U2") (pin "6") (pinfunction "OUT_6") (pintype "passive"))
    )
    (net (code "38") (name "Net-(D4-B)") (class "Default")
      (node (ref "D4") (pin "4") (pinfunction "B_4") (pintype "passive"))
      (node (ref "R11") (pin "1") (pinfunction "1_1") (pintype "passive"))
    )
    (net (code "39") (name "Net-(D4-G)") (class "Default")
      (node (ref "D4") (pin "3") (pinfunction "G_3") (pintype "passive"))
      (node (ref "R12") (pin "1") (pinfunction "1_1") (pintype "passive"))
    )
    (net (code "40") (name "Net-(D4-R)") (class "Default")
      (node (ref "D4") (pin "2") (pinfunction "R_2") (pintype "passive"))
      (node (ref "R13") (pin "1") (pinfunction "1_1") (pintype "passive"))
    )
    (net (code "41") (name "Net-(Q2-D)") (class "Default")
      (node (ref "C5") (pin "2") (pinfunction "2_2") (pintype "passive"))
      (node (ref "Q2") (pin "3") (pinfunction "D_3") (pintype "passive"))
      (node (ref "R2") (pin "2") (pinfunction "2_2") (pintype "passive"))
      (node (ref "R5") (pin "2") (pinfunction "2_2") (pintype "passive"))
      (node (ref "U2") (pin "3") (pinfunction "EN_3") (pintype "passive"))
      (node (ref "U2") (pin "4") (pinfunction "~{FAULT}_4") (pintype "passive"))
    )
    (net (code "42") (name "Net-(R8-Pad2)") (class "Default")
      (node (ref "R8") (pin "2") (pinfunction "2_2") (pintype "passive"))
      (node (ref "SW2") (pin "3") (pinfunction "3_3") (pintype "passive"))
      (node (ref "SW2") (pin "4") (pinfunction "4_4") (pintype "passive"))
    )
    (net (code "43") (name "Net-(U2-ILIM)") (class "Default")
      (node (ref "R6") (pin "2") (pinfunction "2_2") (pintype "passive"))
      (node (ref "U2") (pin "5") (pinfunction "ILIM_5") (pintype "passive"))
    )
    (net (code "44") (name "Net-(X1-OSC1{slash}OSC2)") (class "Default")
      (node (ref "C21") (pin "1") (pinfunction "1_1") (pintype "passive"))
      (node (ref "R9") (pin "1") (pinfunction "1_1") (pintype "passive"))
      (node (ref "X1") (pin "1") (pinfunction "OSC1/OSC2_1") (pintype "passive"))
    )
    (net (code "45") (name "VUSB") (class "Default")
      (node (ref "C1") (pin "2") (pinfunction "2_2") (pintype "passive"))
      (node (ref "C4") (pin "2") (pinfunction "2_2") (pintype "passive"))
      (node (ref "D8") (pin "1") (pinfunction "K_1") (pintype "passive"))
      (node (ref "J3") (pin "A4") (pinfunction "VBUS_A4") (pintype "passive"))
      (node (ref "J3") (pin "A9") (pinfunction "VBUS_A9") (pintype "passive"))
      (node (ref "J3") (pin "B4") (pinfunction "VBUS_B4") (pintype "passive"))
      (node (ref "J3") (pin "B9") (pinfunction "VBUS_B9") (pintype "passive"))
      (node (ref "U1") (pin "1") (pinfunction "IN_1") (pintype "passive"))
      (node (ref "U1") (pin "3") (pinfunction "EN_3") (pintype "passive"))
      (node (ref "U2") (pin "1") (pinfunction "IN_1") (pintype "passive"))
    )
    (net (code "46") (name "unconnected-(J3-SBU1-PadA8)") (class "Default")
      (node (ref "J3") (pin "A8") (pinfunction "SBU1_A8") (pintype "passive+no_connect"))
    )
    (net (code "47") (name "unconnected-(J3-SBU2-PadB8)") (class "Default")
      (node (ref "J3") (pin "B8") (pinfunction "SBU2_B8") (pintype "passive+no_connect"))
    )
    (net (code "48") (name "unconnected-(U3-GPIO0-Pad2)") (class "Default")
      (node (ref "U3") (pin "2") (pinfunction "GPIO0_2") (pintype "passive+no_connect"))
    )
    (net (code "49") (name "unconnected-(U3-GPIO1-Pad3)") (class "Default")
      (node (ref "U3") (pin "3") (pinfunction "GPIO1_3") (pintype "passive+no_connect"))
    )
    (net (code "50") (name "unconnected-(U3-GPIO7-Pad9)") (class "Default")
      (node (ref "U3") (pin "9") (pinfunction "GPIO7_9") (pintype "passive+no_connect"))
    )
    (net (code "51") (name "unconnected-(U3-GPIO8-Pad11)") (class "Default")
      (node (ref "U3") (pin "11") (pinfunction "GPIO8_11") (pintype "passive+no_connect"))
    )
    (net (code "52") (name "unconnected-(U3-GPIO10-Pad13)") (class "Default")
      (node (ref "U3") (pin "13") (pinfunction "GPIO10_13") (pintype "passive+no_connect"))
    )
    (net (code "53") (name "unconnected-(U3-GPIO12-Pad15)") (class "Default")
      (node (ref "U3") (pin "15") (pinfunction "GPIO12_15") (pintype "passive+no_connect"))
    )
    (net (code "54") (name "unconnected-(U3-GPIO14-Pad17)") (class "Default")
      (node (ref "U3") (pin "17") (pinfunction "GPIO14_17") (pintype "passive+no_connect"))
    )
    (net (code "55") (name "unconnected-(U3-GPIO16-Pad27)") (class "Default")
      (node (ref "U3") (pin "27") (pinfunction "GPIO16_27") (pintype "passive+no_connect"))
    )
    (net (code "56") (name "unconnected-(U3-GPIO17-Pad28)") (class "Default")
      (node (ref "U3") (pin "28") (pinfunction "GPIO17_28") (pintype "passive+no_connect"))
    )
    (net (code "57") (name "unconnected-(U3-GPIO18-Pad29)") (class "Default")
      (node (ref "U3") (pin "29") (pinfunction "GPIO18_29") (pintype "passive+no_connect"))
    )
    (net (code "58") (name "unconnected-(U3-GPIO20-Pad31)") (class "Default")
      (node (ref "U3") (pin "31") (pinfunction "GPIO20_31") (pintype "passive+no_connect"))
    )
    (net (code "59") (name "unconnected-(U3-GPIO21-Pad32)") (class "Default")
      (node (ref "U3") (pin "32") (pinfunction "GPIO21_32") (pintype "passive+no_connect"))
    )
    (net (code "60") (name "unconnected-(U3-GPIO22-Pad34)") (class "Default")
      (node (ref "U3") (pin "34") (pinfunction "GPIO22_34") (pintype "passive+no_connect"))
    )
    (net (code "61") (name "unconnected-(U3-GPIO23-Pad35)") (class "Default")
      (node (ref "U3") (pin "35") (pinfunction "GPIO23_35") (pintype "passive+no_connect"))
    )
    (net (code "62") (name "unconnected-(U3-GPIO24-Pad36)") (class "Default")
      (node (ref "U3") (pin "36") (pinfunction "GPIO24_36") (pintype "passive+no_connect"))
    )
  )
)
